# transceiver_2.net
KiCad netlist of a schematic drawn in EAGLE
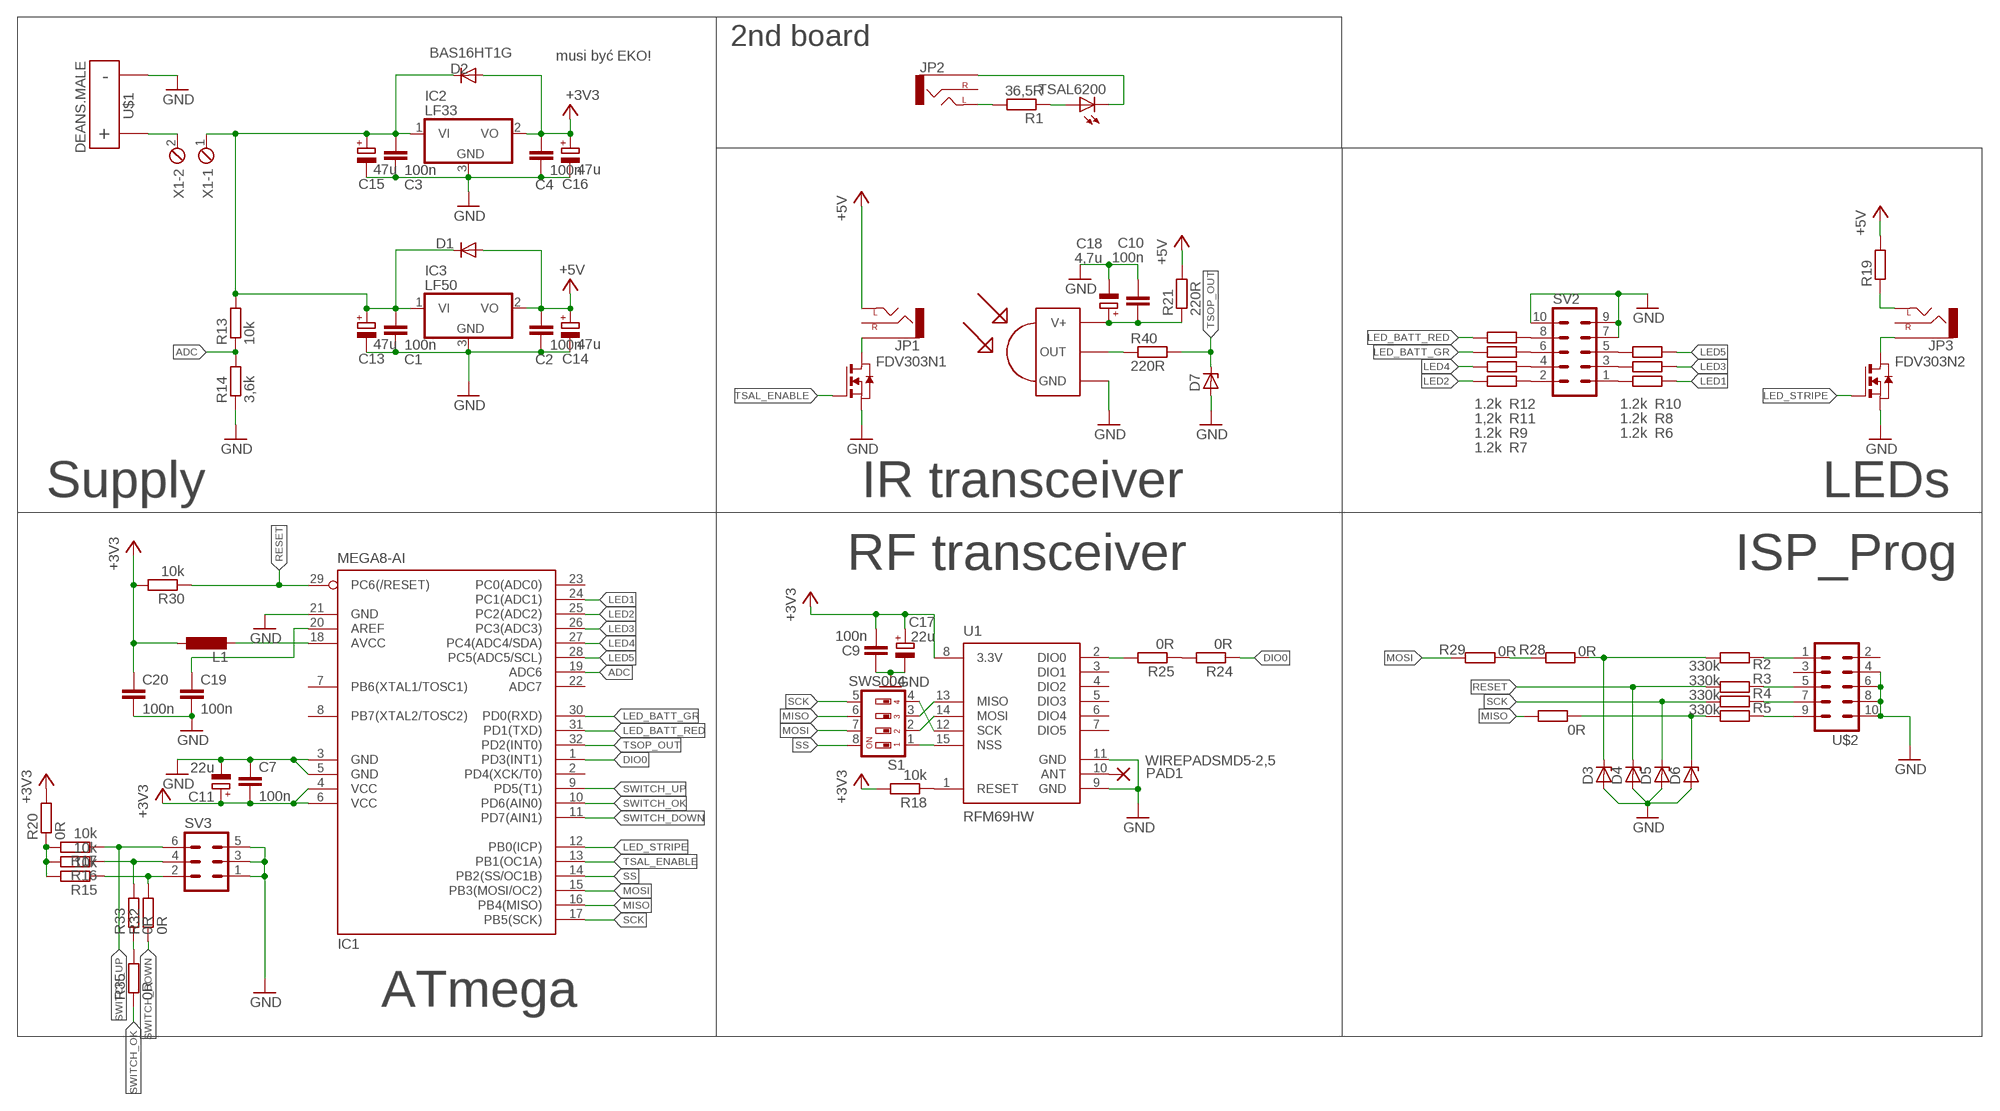
[diagram p0: schematic, sheet 1]

(export (version "E")
  (design (tool "Eeschema 10.0.6"))
  (components
    (comp (ref "C1")
      (value "100n")
      (footprint "eagle-import:C0805")
      (libsource (lib "eagle-import") (part "C-EUC0805"))
    )
    (comp (ref "C2")
      (value "100n")
      (footprint "eagle-import:C0805")
      (libsource (lib "eagle-import") (part "C-EUC0805"))
    )
    (comp (ref "C3")
      (value "100n")
      (footprint "eagle-import:C0805")
      (libsource (lib "eagle-import") (part "C-EUC0805"))
    )
    (comp (ref "C4")
      (value "100n")
      (footprint "eagle-import:C0805")
      (libsource (lib "eagle-import") (part "C-EUC0805"))
    )
    (comp (ref "C7")
      (value "100n")
      (footprint "eagle-import:C0805")
      (libsource (lib "eagle-import") (part "C-EUC0805"))
    )
    (comp (ref "C9")
      (value "100n")
      (footprint "eagle-import:C0805")
      (libsource (lib "eagle-import") (part "C-EUC0805"))
    )
    (comp (ref "C10")
      (value "100n")
      (footprint "eagle-import:C0805")
      (libsource (lib "eagle-import") (part "C-EUC0805"))
    )
    (comp (ref "C11")
      (value "22u")
      (footprint "eagle-import:E2,5-5")
      (libsource (lib "eagle-import") (part "CPOL-EUE2.5-5"))
    )
    (comp (ref "C13")
      (value "47u")
      (footprint "eagle-import:E2,5-5")
      (libsource (lib "eagle-import") (part "CPOL-EUE2.5-5"))
    )
    (comp (ref "C14")
      (value "47u")
      (footprint "eagle-import:E2,5-5")
      (libsource (lib "eagle-import") (part "CPOL-EUE2.5-5"))
    )
    (comp (ref "C15")
      (value "47u")
      (footprint "eagle-import:E2,5-5")
      (libsource (lib "eagle-import") (part "CPOL-EUE2.5-5"))
    )
    (comp (ref "C16")
      (value "47u")
      (footprint "eagle-import:E2,5-5")
      (libsource (lib "eagle-import") (part "CPOL-EUE2.5-5"))
    )
    (comp (ref "C17")
      (value "22u")
      (footprint "eagle-import:E2,5-5")
      (libsource (lib "eagle-import") (part "CPOL-EUE2.5-5"))
    )
    (comp (ref "C18")
      (value "4,7u")
      (footprint "eagle-import:E2,5-5")
      (libsource (lib "eagle-import") (part "CPOL-EUE2.5-5"))
    )
    (comp (ref "C19")
      (value "100n")
      (footprint "eagle-import:C0805")
      (libsource (lib "eagle-import") (part "C-EUC0805"))
    )
    (comp (ref "C20")
      (value "100n")
      (footprint "eagle-import:C0805")
      (libsource (lib "eagle-import") (part "C-EUC0805"))
    )
    (comp (ref "D1")
      (value "BAS16HT1G")
      (footprint "eagle-import:SOD-323")
      (libsource (lib "eagle-import") (part "DIODESOD"))
    )
    (comp (ref "D2")
      (value "BAS16HT1G")
      (footprint "eagle-import:SOD-323")
      (libsource (lib "eagle-import") (part "DIODESOD"))
    )
    (comp (ref "D3")
      (value "ZENER-DIODESOD80C")
      (footprint "eagle-import:SOD80C")
      (libsource (lib "eagle-import") (part "ZENER-DIODESOD80C"))
    )
    (comp (ref "D4")
      (value "ZENER-DIODESOD80C")
      (footprint "eagle-import:SOD80C")
      (libsource (lib "eagle-import") (part "ZENER-DIODESOD80C"))
    )
    (comp (ref "D5")
      (value "ZENER-DIODESOD80C")
      (footprint "eagle-import:SOD80C")
      (libsource (lib "eagle-import") (part "ZENER-DIODESOD80C"))
    )
    (comp (ref "D6")
      (value "ZENER-DIODESOD80C")
      (footprint "eagle-import:SOD80C")
      (libsource (lib "eagle-import") (part "ZENER-DIODESOD80C"))
    )
    (comp (ref "D7")
      (value "ZENER-DIODESOD80C")
      (footprint "eagle-import:SOD80C")
      (libsource (lib "eagle-import") (part "ZENER-DIODESOD80C"))
    )
    (comp (ref "FDV303N1")
      (value "NMOSSOT23")
      (footprint "eagle-import:SOT-23")
      (libsource (lib "eagle-import") (part "NMOSSOT23"))
    )
    (comp (ref "FDV303N2")
      (value "NMOSSOT23")
      (footprint "eagle-import:SOT-23")
      (libsource (lib "eagle-import") (part "NMOSSOT23"))
    )
    (comp (ref "IC1")
      (value "MEGA8-AI")
      (footprint "eagle-import:TQFP32-08")
      (fields (field (name "MPN") "ATMEGA8-16AU"))
      (libsource (lib "eagle-import") (part "MEGA8-AI"))
    )
    (comp (ref "IC2")
      (value "LF33")
      (footprint "eagle-import:TO252")
      (libsource (lib "eagle-import") (part "78DT05"))
    )
    (comp (ref "IC3")
      (value "LF50")
      (footprint "eagle-import:TO252")
      (libsource (lib "eagle-import") (part "78DT05"))
    )
    (comp (ref "JP1")
      (value "AUDIO-JACKPTH")
      (footprint "eagle-import:AUDIO-JACK")
      (libsource (lib "eagle-import") (part "AUDIO-JACKPTH"))
    )
    (comp (ref "JP2")
      (value "AUDIO-JACKPTH")
      (footprint "eagle-import:AUDIO-JACK")
      (libsource (lib "eagle-import") (part "AUDIO-JACKPTH"))
    )
    (comp (ref "JP3")
      (value "AUDIO-JACKPTH")
      (footprint "eagle-import:AUDIO-JACK")
      (libsource (lib "eagle-import") (part "AUDIO-JACKPTH"))
    )
    (comp (ref "L1")
      (value "L-EU0204V")
      (footprint "eagle-import:0204V")
      (libsource (lib "eagle-import") (part "L-EU0204V"))
    )
    (comp (ref "PAD1")
      (value "WIREPADSMD5-2,5")
      (footprint "eagle-import:5-2,5")
      (libsource (lib "eagle-import") (part "WIREPADSMD5-2,5"))
    )
    (comp (ref "R1")
      (value "36,5R")
      (footprint "eagle-import:R0805")
      (libsource (lib "eagle-import") (part "resistor_R-EU_R0805"))
    )
    (comp (ref "R2")
      (value "330k")
      (footprint "eagle-import:R0805")
      (libsource (lib "eagle-import") (part "resistor_R-EU_R0805"))
    )
    (comp (ref "R3")
      (value "330k")
      (footprint "eagle-import:R0805")
      (libsource (lib "eagle-import") (part "resistor_R-EU_R0805"))
    )
    (comp (ref "R4")
      (value "330k")
      (footprint "eagle-import:R0805")
      (libsource (lib "eagle-import") (part "resistor_R-EU_R0805"))
    )
    (comp (ref "R5")
      (value "330k")
      (footprint "eagle-import:R0805")
      (libsource (lib "eagle-import") (part "resistor_R-EU_R0805"))
    )
    (comp (ref "R6")
      (value "1.2k")
      (footprint "eagle-import:R0805")
      (libsource (lib "eagle-import") (part "resistor_R-EU_R0805"))
    )
    (comp (ref "R7")
      (value "1.2k")
      (footprint "eagle-import:R0805")
      (libsource (lib "eagle-import") (part "resistor_R-EU_R0805"))
    )
    (comp (ref "R8")
      (value "1.2k")
      (footprint "eagle-import:R0805")
      (libsource (lib "eagle-import") (part "resistor_R-EU_R0805"))
    )
    (comp (ref "R9")
      (value "1.2k")
      (footprint "eagle-import:R0805")
      (libsource (lib "eagle-import") (part "resistor_R-EU_R0805"))
    )
    (comp (ref "R10")
      (value "1.2k")
      (footprint "eagle-import:R0805")
      (libsource (lib "eagle-import") (part "resistor_R-EU_R0805"))
    )
    (comp (ref "R11")
      (value "1,2k")
      (footprint "eagle-import:R0805")
      (libsource (lib "eagle-import") (part "resistor_R-EU_R0805"))
    )
    (comp (ref "R12")
      (value "1.2k")
      (footprint "eagle-import:R0805")
      (libsource (lib "eagle-import") (part "resistor_R-EU_R0805"))
    )
    (comp (ref "R13")
      (value "10k")
      (footprint "eagle-import:R0805")
      (libsource (lib "eagle-import") (part "resistor_R-EU_R0805"))
    )
    (comp (ref "R14")
      (value "3,6k")
      (footprint "eagle-import:R0805")
      (libsource (lib "eagle-import") (part "resistor_R-EU_R0805"))
    )
    (comp (ref "R15")
      (value "10k")
      (footprint "eagle-import:R0805")
      (libsource (lib "eagle-import") (part "resistor_R-EU_R0805"))
    )
    (comp (ref "R16")
      (value "10k")
      (footprint "eagle-import:R0805")
      (libsource (lib "eagle-import") (part "resistor_R-EU_R0805"))
    )
    (comp (ref "R17")
      (value "10k")
      (footprint "eagle-import:R0805")
      (libsource (lib "eagle-import") (part "resistor_R-EU_R0805"))
    )
    (comp (ref "R18")
      (value "10k")
      (footprint "eagle-import:R0805")
      (libsource (lib "eagle-import") (part "resistor_R-EU_R0805"))
    )
    (comp (ref "R19")
      (value "R-EU_R0805")
      (footprint "eagle-import:R0805")
      (libsource (lib "eagle-import") (part "resistor_R-EU_R0805"))
    )
    (comp (ref "R20")
      (value "0R")
      (footprint "eagle-import:R1206")
      (libsource (lib "eagle-import") (part "R-EU_R1206"))
    )
    (comp (ref "R21")
      (value "220R")
      (footprint "eagle-import:R0805")
      (libsource (lib "eagle-import") (part "resistor_R-EU_R0805"))
    )
    (comp (ref "R24")
      (value "0R")
      (footprint "eagle-import:R1206")
      (libsource (lib "eagle-import") (part "R-EU_R1206"))
    )
    (comp (ref "R25")
      (value "0R")
      (footprint "eagle-import:R1206")
      (libsource (lib "eagle-import") (part "R-EU_R1206"))
    )
    (comp (ref "R28")
      (value "0R")
      (footprint "eagle-import:R1206")
      (libsource (lib "eagle-import") (part "R-EU_R1206"))
    )
    (comp (ref "R29")
      (value "0R")
      (footprint "eagle-import:R1206")
      (libsource (lib "eagle-import") (part "R-EU_R1206"))
    )
    (comp (ref "R30")
      (value "10k")
      (footprint "eagle-import:R0805")
      (libsource (lib "eagle-import") (part "resistor_R-EU_R0805"))
    )
    (comp (ref "R31")
      (value "0R")
      (footprint "eagle-import:R1206")
      (libsource (lib "eagle-import") (part "R-EU_R1206"))
    )
    (comp (ref "R32")
      (value "0R")
      (footprint "eagle-import:R1206")
      (libsource (lib "eagle-import") (part "R-EU_R1206"))
    )
    (comp (ref "R33")
      (value "0R")
      (footprint "eagle-import:R1206")
      (libsource (lib "eagle-import") (part "R-EU_R1206"))
    )
    (comp (ref "R35")
      (value "0R")
      (footprint "eagle-import:R1206")
      (libsource (lib "eagle-import") (part "R-EU_R1206"))
    )
    (comp (ref "R40")
      (value "220R")
      (footprint "eagle-import:R0805")
      (libsource (lib "eagle-import") (part "resistor_R-EU_R0805"))
    )
    (comp (ref "S1")
      (value "SWS004")
      (footprint "eagle-import:SMS-004")
      (libsource (lib "eagle-import") (part "SWS004"))
    )
    (comp (ref "SV2")
      (value "ML10")
      (footprint "eagle-import:ML10")
      (libsource (lib "eagle-import") (part "ML10"))
    )
    (comp (ref "SV3")
      (value "ML6")
      (footprint "eagle-import:ML6")
      (libsource (lib "eagle-import") (part "ML6"))
    )
    (comp (ref "TSAL6200")
      (value "LED5MM")
      (footprint "eagle-import:LED5MM")
      (libsource (lib "eagle-import") (part "LED5MM"))
    )
    (comp (ref "TSOP")
      (value "TSOP1736")
      (footprint "eagle-import:TSOP17XX")
      (libsource (lib "eagle-import") (part "TSOP1736"))
    )
    (comp (ref "U$1")
      (value "DEANS.MALE")
      (footprint "eagle-import:DEANSM")
      (libsource (lib "eagle-import") (part "DEANS.MALE"))
    )
    (comp (ref "U$2")
      (value "ML10")
      (footprint "eagle-import:ML10")
      (libsource (lib "eagle-import") (part "ML10"))
    )
    (comp (ref "U1")
      (value "RFM69HW")
      (footprint "eagle-import:RFM69W-XXXS2")
      (libsource (lib "eagle-import") (part "RFM69HW"))
    )
    (comp (ref "X1")
      (value "MPT2")
      (footprint "eagle-import:2POL254")
      (libsource (lib "eagle-import") (part "MPT2"))
    )
  )
  (nets
    (net (code "1") (name "+3V3") (class "Default")
      (node (ref "C11") (pin "+") (pinfunction "+_+") (pintype "passive"))
      (node (ref "C16") (pin "+") (pinfunction "+_+") (pintype "passive"))
      (node (ref "C17") (pin "+") (pinfunction "+_+") (pintype "passive"))
      (node (ref "C20") (pin "1") (pinfunction "1_1") (pintype "passive"))
      (node (ref "C4") (pin "1") (pinfunction "1_1") (pintype "passive"))
      (node (ref "C7") (pin "2") (pinfunction "2_2") (pintype "passive"))
      (node (ref "C9") (pin "2") (pinfunction "2_2") (pintype "passive"))
      (node (ref "D2") (pin "2") (pinfunction "A_2") (pintype "passive"))
      (node (ref "IC1") (pin "4") (pinfunction "VCC_4") (pintype "power_in"))
      (node (ref "IC1") (pin "6") (pinfunction "VCC_6") (pintype "power_in"))
      (node (ref "IC2") (pin "2") (pinfunction "VO_2") (pintype "passive"))
      (node (ref "L1") (pin "1") (pinfunction "1_1") (pintype "passive"))
      (node (ref "R18") (pin "2") (pinfunction "2_2") (pintype "passive"))
      (node (ref "R20") (pin "2") (pinfunction "2_2") (pintype "passive"))
      (node (ref "R30") (pin "2") (pinfunction "2_2") (pintype "passive"))
      (node (ref "U1") (pin "8") (pinfunction "3.3V_8") (pintype "power_in"))
    )
    (net (code "2") (name "+5V") (class "Default")
      (node (ref "C14") (pin "+") (pinfunction "+_+") (pintype "passive"))
      (node (ref "C2") (pin "1") (pinfunction "1_1") (pintype "passive"))
      (node (ref "D1") (pin "2") (pinfunction "A_2") (pintype "passive"))
      (node (ref "IC3") (pin "2") (pinfunction "VO_2") (pintype "passive"))
      (node (ref "JP1") (pin "TIP") (pinfunction "LEFT_TIP") (pintype "bidirectional"))
      (node (ref "R19") (pin "2") (pinfunction "2_2") (pintype "passive"))
      (node (ref "R21") (pin "2") (pinfunction "2_2") (pintype "passive"))
    )
    (net (code "3") (name "ADC") (class "Default")
      (node (ref "IC1") (pin "19") (pinfunction "ADC6_19") (pintype "bidirectional"))
      (node (ref "R13") (pin "1") (pinfunction "1_1") (pintype "passive"))
      (node (ref "R14") (pin "2") (pinfunction "2_2") (pintype "passive"))
    )
    (net (code "4") (name "DIO0") (class "Default")
      (node (ref "IC1") (pin "1") (pinfunction "PD3(INT1)_1") (pintype "bidirectional"))
      (node (ref "R24") (pin "1") (pinfunction "1_1") (pintype "passive"))
    )
    (net (code "5") (name "GND") (class "Default")
      (node (ref "C1") (pin "2") (pinfunction "2_2") (pintype "passive"))
      (node (ref "C10") (pin "2") (pinfunction "2_2") (pintype "passive"))
      (node (ref "C11") (pin "-") (pinfunction "-_-") (pintype "passive"))
      (node (ref "C13") (pin "-") (pinfunction "-_-") (pintype "passive"))
      (node (ref "C14") (pin "-") (pinfunction "-_-") (pintype "passive"))
      (node (ref "C15") (pin "-") (pinfunction "-_-") (pintype "passive"))
      (node (ref "C16") (pin "-") (pinfunction "-_-") (pintype "passive"))
      (node (ref "C17") (pin "-") (pinfunction "-_-") (pintype "passive"))
      (node (ref "C18") (pin "-") (pinfunction "-_-") (pintype "passive"))
      (node (ref "C19") (pin "2") (pinfunction "2_2") (pintype "passive"))
      (node (ref "C2") (pin "2") (pinfunction "2_2") (pintype "passive"))
      (node (ref "C20") (pin "2") (pinfunction "2_2") (pintype "passive"))
      (node (ref "C3") (pin "2") (pinfunction "2_2") (pintype "passive"))
      (node (ref "C4") (pin "2") (pinfunction "2_2") (pintype "passive"))
      (node (ref "C7") (pin "1") (pinfunction "1_1") (pintype "passive"))
      (node (ref "C9") (pin "1") (pinfunction "1_1") (pintype "passive"))
      (node (ref "D3") (pin "A") (pinfunction "A_A") (pintype "passive"))
      (node (ref "D4") (pin "A") (pinfunction "A_A") (pintype "passive"))
      (node (ref "D5") (pin "A") (pinfunction "A_A") (pintype "passive"))
      (node (ref "D6") (pin "A") (pinfunction "A_A") (pintype "passive"))
      (node (ref "D7") (pin "A") (pinfunction "A_A") (pintype "passive"))
      (node (ref "FDV303N1") (pin "2") (pinfunction "S_2") (pintype "passive"))
      (node (ref "FDV303N2") (pin "2") (pinfunction "S_2") (pintype "passive"))
      (node (ref "IC1") (pin "21") (pinfunction "GND_21") (pintype "power_in"))
      (node (ref "IC1") (pin "3") (pinfunction "GND_3") (pintype "power_in"))
      (node (ref "IC1") (pin "5") (pinfunction "GND_5") (pintype "power_in"))
      (node (ref "IC2") (pin "3") (pinfunction "GND_3") (pintype "passive"))
      (node (ref "IC3") (pin "3") (pinfunction "GND_3") (pintype "passive"))
      (node (ref "R14") (pin "1") (pinfunction "1_1") (pintype "passive"))
      (node (ref "SV2") (pin "10") (pinfunction "10_10") (pintype "passive"))
      (node (ref "SV2") (pin "7") (pinfunction "7_7") (pintype "passive"))
      (node (ref "SV2") (pin "9") (pinfunction "9_9") (pintype "passive"))
      (node (ref "SV3") (pin "1") (pinfunction "1_1") (pintype "passive"))
      (node (ref "SV3") (pin "3") (pinfunction "3_3") (pintype "passive"))
      (node (ref "SV3") (pin "5") (pinfunction "5_5") (pintype "passive"))
      (node (ref "TSOP") (pin "GND") (pinfunction "GND_GND") (pintype "bidirectional"))
      (node (ref "U$1") (pin "P$NEG") (pinfunction "P$NEG_P$NEG") (pintype "bidirectional"))
      (node (ref "U$2") (pin "10") (pinfunction "10_10") (pintype "passive"))
      (node (ref "U$2") (pin "4") (pinfunction "4_4") (pintype "passive"))
      (node (ref "U$2") (pin "6") (pinfunction "6_6") (pintype "passive"))
      (node (ref "U$2") (pin "8") (pinfunction "8_8") (pintype "passive"))
      (node (ref "U1") (pin "11") (pinfunction "GND_11") (pintype "power_in"))
      (node (ref "U1") (pin "9") (pinfunction "GND_9") (pintype "power_in"))
    )
    (net (code "6") (name "LED1") (class "Default")
      (node (ref "IC1") (pin "24") (pinfunction "PC1(ADC1)_24") (pintype "bidirectional"))
      (node (ref "R6") (pin "1") (pinfunction "1_1") (pintype "passive"))
    )
    (net (code "7") (name "LED2") (class "Default")
      (node (ref "IC1") (pin "25") (pinfunction "PC2(ADC2)_25") (pintype "bidirectional"))
      (node (ref "R7") (pin "1") (pinfunction "1_1") (pintype "passive"))
    )
    (net (code "8") (name "LED3") (class "Default")
      (node (ref "IC1") (pin "26") (pinfunction "PC3(ADC3)_26") (pintype "bidirectional"))
      (node (ref "R8") (pin "1") (pinfunction "1_1") (pintype "passive"))
    )
    (net (code "9") (name "LED4") (class "Default")
      (node (ref "IC1") (pin "27") (pinfunction "PC4(ADC4/SDA)_27") (pintype "bidirectional"))
      (node (ref "R9") (pin "1") (pinfunction "1_1") (pintype "passive"))
    )
    (net (code "10") (name "LED5") (class "Default")
      (node (ref "IC1") (pin "28") (pinfunction "PC5(ADC5/SCL)_28") (pintype "bidirectional"))
      (node (ref "R10") (pin "1") (pinfunction "1_1") (pintype "passive"))
    )
    (net (code "11") (name "LED_BATT_GR") (class "Default")
      (node (ref "IC1") (pin "30") (pinfunction "PD0(RXD)_30") (pintype "bidirectional"))
      (node (ref "R11") (pin "1") (pinfunction "1_1") (pintype "passive"))
    )
    (net (code "12") (name "LED_BATT_RED") (class "Default")
      (node (ref "IC1") (pin "31") (pinfunction "PD1(TXD)_31") (pintype "bidirectional"))
      (node (ref "R12") (pin "1") (pinfunction "1_1") (pintype "passive"))
    )
    (net (code "13") (name "LED_STRIPE") (class "Default")
      (node (ref "FDV303N2") (pin "3") (pinfunction "G_3") (pintype "passive"))
      (node (ref "IC1") (pin "12") (pinfunction "PB0(ICP)_12") (pintype "bidirectional"))
    )
    (net (code "14") (name "MISO") (class "Default")
      (node (ref "IC1") (pin "16") (pinfunction "PB4(MISO)_16") (pintype "bidirectional"))
      (node (ref "R31") (pin "2") (pinfunction "2_2") (pintype "passive"))
      (node (ref "S1") (pin "6") (pinfunction "6_6") (pintype "passive"))
    )
    (net (code "15") (name "MOSI") (class "Default")
      (node (ref "IC1") (pin "15") (pinfunction "PB3(MOSI/OC2)_15") (pintype "bidirectional"))
      (node (ref "R29") (pin "2") (pinfunction "2_2") (pintype "passive"))
      (node (ref "S1") (pin "7") (pinfunction "7_7") (pintype "passive"))
    )
    (net (code "16") (name "Net-(C10-Pad1)") (class "Default")
      (node (ref "C10") (pin "1") (pinfunction "1_1") (pintype "passive"))
      (node (ref "C18") (pin "+") (pinfunction "+_+") (pintype "passive"))
      (node (ref "R21") (pin "1") (pinfunction "1_1") (pintype "passive"))
      (node (ref "TSOP") (pin "V+") (pinfunction "V+_V+") (pintype "bidirectional"))
    )
    (net (code "17") (name "Net-(D1-C)") (class "Default")
      (node (ref "C1") (pin "1") (pinfunction "1_1") (pintype "passive"))
      (node (ref "C13") (pin "+") (pinfunction "+_+") (pintype "passive"))
      (node (ref "C15") (pin "+") (pinfunction "+_+") (pintype "passive"))
      (node (ref "C3") (pin "1") (pinfunction "1_1") (pintype "passive"))
      (node (ref "D1") (pin "1") (pinfunction "C_1") (pintype "passive"))
      (node (ref "D2") (pin "1") (pinfunction "C_1") (pintype "passive"))
      (node (ref "IC2") (pin "1") (pinfunction "VI_1") (pintype "input"))
      (node (ref "IC3") (pin "1") (pinfunction "VI_1") (pintype "input"))
      (node (ref "R13") (pin "2") (pinfunction "2_2") (pintype "passive"))
      (node (ref "X1") (pin "1") (pinfunction "1_1") (pintype "passive"))
    )
    (net (code "18") (name "Net-(D3-PadC)") (class "Default")
      (node (ref "D3") (pin "C") (pinfunction "C_C") (pintype "passive"))
      (node (ref "R2") (pin "2") (pinfunction "2_2") (pintype "passive"))
      (node (ref "R28") (pin "1") (pinfunction "1_1") (pintype "passive"))
    )
    (net (code "19") (name "Net-(D6-PadC)") (class "Default")
      (node (ref "D6") (pin "C") (pinfunction "C_C") (pintype "passive"))
      (node (ref "R31") (pin "1") (pinfunction "1_1") (pintype "passive"))
      (node (ref "R5") (pin "2") (pinfunction "2_2") (pintype "passive"))
    )
    (net (code "20") (name "Net-(FDV303N1-D)") (class "Default")
      (node (ref "FDV303N1") (pin "1") (pinfunction "D_1") (pintype "passive"))
      (node (ref "JP1") (pin "SLEEVE") (pinfunction "SLEEVE_SLEEVE") (pintype "bidirectional"))
    )
    (net (code "21") (name "Net-(FDV303N2-D)") (class "Default")
      (node (ref "FDV303N2") (pin "1") (pinfunction "D_1") (pintype "passive"))
      (node (ref "JP3") (pin "SLEEVE") (pinfunction "SLEEVE_SLEEVE") (pintype "bidirectional"))
    )
    (net (code "22") (name "Net-(IC1-AREF)") (class "Default")
      (node (ref "C19") (pin "1") (pinfunction "1_1") (pintype "passive"))
      (node (ref "IC1") (pin "20") (pinfunction "AREF_20") (pintype "passive"))
    )
    (net (code "23") (name "Net-(IC1-AVCC)") (class "Default")
      (node (ref "IC1") (pin "18") (pinfunction "AVCC_18") (pintype "power_in"))
      (node (ref "L1") (pin "2") (pinfunction "2_2") (pintype "passive"))
    )
    (net (code "24") (name "Net-(JP2-LEFT)") (class "Default")
      (node (ref "JP2") (pin "TIP") (pinfunction "LEFT_TIP") (pintype "bidirectional"))
      (node (ref "R1") (pin "2") (pinfunction "2_2") (pintype "passive"))
    )
    (net (code "25") (name "Net-(JP3-LEFT)") (class "Default")
      (node (ref "JP3") (pin "TIP") (pinfunction "LEFT_TIP") (pintype "bidirectional"))
      (node (ref "R19") (pin "1") (pinfunction "1_1") (pintype "passive"))
    )
    (net (code "26") (name "Net-(PAD1-P)") (class "Default")
      (node (ref "PAD1") (pin "1") (pinfunction "P_1") (pintype "passive"))
      (node (ref "U1") (pin "10") (pinfunction "ANT_10") (pintype "passive"))
    )
    (net (code "27") (name "Net-(R1-Pad1)") (class "Default")
      (node (ref "R1") (pin "1") (pinfunction "1_1") (pintype "passive"))
      (node (ref "TSAL6200") (pin "A") (pinfunction "A_A") (pintype "passive"))
    )
    (net (code "28") (name "Net-(R2-Pad1)") (class "Default")
      (node (ref "R2") (pin "1") (pinfunction "1_1") (pintype "passive"))
      (node (ref "U$2") (pin "1") (pinfunction "1_1") (pintype "passive"))
    )
    (net (code "29") (name "Net-(R3-Pad1)") (class "Default")
      (node (ref "R3") (pin "1") (pinfunction "1_1") (pintype "passive"))
      (node (ref "U$2") (pin "5") (pinfunction "5_5") (pintype "passive"))
    )
    (net (code "30") (name "Net-(R4-Pad1)") (class "Default")
      (node (ref "R4") (pin "1") (pinfunction "1_1") (pintype "passive"))
      (node (ref "U$2") (pin "7") (pinfunction "7_7") (pintype "passive"))
    )
    (net (code "31") (name "Net-(R5-Pad1)") (class "Default")
      (node (ref "R5") (pin "1") (pinfunction "1_1") (pintype "passive"))
      (node (ref "U$2") (pin "9") (pinfunction "9_9") (pintype "passive"))
    )
    (net (code "32") (name "Net-(R6-Pad2)") (class "Default")
      (node (ref "R6") (pin "2") (pinfunction "2_2") (pintype "passive"))
      (node (ref "SV2") (pin "1") (pinfunction "1_1") (pintype "passive"))
    )
    (net (code "33") (name "Net-(R7-Pad2)") (class "Default")
      (node (ref "R7") (pin "2") (pinfunction "2_2") (pintype "passive"))
      (node (ref "SV2") (pin "2") (pinfunction "2_2") (pintype "passive"))
    )
    (net (code "34") (name "Net-(R8-Pad2)") (class "Default")
      (node (ref "R8") (pin "2") (pinfunction "2_2") (pintype "passive"))
      (node (ref "SV2") (pin "3") (pinfunction "3_3") (pintype "passive"))
    )
    (net (code "35") (name "Net-(R9-Pad2)") (class "Default")
      (node (ref "R9") (pin "2") (pinfunction "2_2") (pintype "passive"))
      (node (ref "SV2") (pin "4") (pinfunction "4_4") (pintype "passive"))
    )
    (net (code "36") (name "Net-(R10-Pad2)") (class "Default")
      (node (ref "R10") (pin "2") (pinfunction "2_2") (pintype "passive"))
      (node (ref "SV2") (pin "5") (pinfunction "5_5") (pintype "passive"))
    )
    (net (code "37") (name "Net-(R11-Pad2)") (class "Default")
      (node (ref "R11") (pin "2") (pinfunction "2_2") (pintype "passive"))
      (node (ref "SV2") (pin "6") (pinfunction "6_6") (pintype "passive"))
    )
    (net (code "38") (name "Net-(R12-Pad2)") (class "Default")
      (node (ref "R12") (pin "2") (pinfunction "2_2") (pintype "passive"))
      (node (ref "SV2") (pin "8") (pinfunction "8_8") (pintype "passive"))
    )
    (net (code "39") (name "Net-(R15-Pad1)") (class "Default")
      (node (ref "R15") (pin "1") (pinfunction "1_1") (pintype "passive"))
      (node (ref "R32") (pin "2") (pinfunction "2_2") (pintype "passive"))
      (node (ref "SV3") (pin "2") (pinfunction "2_2") (pintype "passive"))
    )
    (net (code "40") (name "Net-(R15-Pad2)") (class "Default")
      (node (ref "R15") (pin "2") (pinfunction "2_2") (pintype "passive"))
      (node (ref "R16") (pin "2") (pinfunction "2_2") (pintype "passive"))
      (node (ref "R17") (pin "2") (pinfunction "2_2") (pintype "passive"))
      (node (ref "R20") (pin "1") (pinfunction "1_1") (pintype "passive"))
    )
    (net (code "41") (name "Net-(R16-Pad1)") (class "Default")
      (node (ref "R16") (pin "1") (pinfunction "1_1") (pintype "passive"))
      (node (ref "R33") (pin "2") (pinfunction "2_2") (pintype "passive"))
      (node (ref "SV3") (pin "4") (pinfunction "4_4") (pintype "passive"))
    )
    (net (code "42") (name "Net-(R24-Pad2)") (class "Default")
      (node (ref "R24") (pin "2") (pinfunction "2_2") (pintype "passive"))
      (node (ref "R25") (pin "1") (pinfunction "1_1") (pintype "passive"))
    )
    (net (code "43") (name "Net-(R28-Pad2)") (class "Default")
      (node (ref "R28") (pin "2") (pinfunction "2_2") (pintype "passive"))
      (node (ref "R29") (pin "1") (pinfunction "1_1") (pintype "passive"))
    )
    (net (code "44") (name "Net-(R33-Pad1)") (class "Default")
      (node (ref "R33") (pin "1") (pinfunction "1_1") (pintype "passive"))
      (node (ref "R35") (pin "2") (pinfunction "2_2") (pintype "passive"))
    )
    (net (code "45") (name "Net-(R40-Pad1)") (class "Default")
      (node (ref "R40") (pin "1") (pinfunction "1_1") (pintype "passive"))
      (node (ref "TSOP") (pin "OUT") (pinfunction "OUT_OUT") (pintype "bidirectional"))
    )
    (net (code "46") (name "Net-(TSAL6200-C)") (class "Default")
      (node (ref "JP2") (pin "SLEEVE") (pinfunction "SLEEVE_SLEEVE") (pintype "bidirectional"))
      (node (ref "TSAL6200") (pin "K") (pinfunction "C_K") (pintype "passive"))
    )
    (net (code "47") (name "Net-(U1-DIO0)") (class "Default")
      (node (ref "R25") (pin "2") (pinfunction "2_2") (pintype "passive"))
      (node (ref "U1") (pin "2") (pinfunction "DIO0_2") (pintype "bidirectional"))
    )
    (net (code "48") (name "Net-(U1-MISO)") (class "Default")
      (node (ref "S1") (pin "3") (pinfunction "3_3") (pintype "passive"))
      (node (ref "U1") (pin "13") (pinfunction "MISO_13") (pintype "bidirectional"))
    )
    (net (code "49") (name "Net-(U1-MOSI)") (class "Default")
      (node (ref "S1") (pin "2") (pinfunction "2_2") (pintype "passive"))
      (node (ref "U1") (pin "14") (pinfunction "MOSI_14") (pintype "input"))
    )
    (net (code "50") (name "Net-(U1-NSS)") (class "Default")
      (node (ref "S1") (pin "1") (pinfunction "1_1") (pintype "passive"))
      (node (ref "U1") (pin "15") (pinfunction "NSS_15") (pintype "input"))
    )
    (net (code "51") (name "Net-(U1-RESET)") (class "Default")
      (node (ref "R18") (pin "1") (pinfunction "1_1") (pintype "passive"))
      (node (ref "U1") (pin "1") (pinfunction "RESET_1") (pintype "input"))
    )
    (net (code "52") (name "Net-(U1-SCK)") (class "Default")
      (node (ref "S1") (pin "4") (pinfunction "4_4") (pintype "passive"))
      (node (ref "U1") (pin "12") (pinfunction "SCK_12") (pintype "input"))
    )
    (net (code "53") (name "Net-(X1B-1)") (class "Default")
      (node (ref "U$1") (pin "P$POS") (pinfunction "P$POS_P$POS") (pintype "bidirectional"))
      (node (ref "X1") (pin "2") (pinfunction "1_2") (pintype "passive"))
    )
    (net (code "54") (name "RESET") (class "Default")
      (node (ref "D4") (pin "C") (pinfunction "C_C") (pintype "passive"))
      (node (ref "IC1") (pin "29") (pinfunction "PC6(/RESET)_29") (pintype "bidirectional"))
      (node (ref "R3") (pin "2") (pinfunction "2_2") (pintype "passive"))
      (node (ref "R30") (pin "1") (pinfunction "1_1") (pintype "passive"))
    )
    (net (code "55") (name "SCK") (class "Default")
      (node (ref "D5") (pin "C") (pinfunction "C_C") (pintype "passive"))
      (node (ref "IC1") (pin "17") (pinfunction "PB5(SCK)_17") (pintype "bidirectional"))
      (node (ref "R4") (pin "2") (pinfunction "2_2") (pintype "passive"))
      (node (ref "S1") (pin "5") (pinfunction "5_5") (pintype "passive"))
    )
    (net (code "56") (name "SS") (class "Default")
      (node (ref "IC1") (pin "14") (pinfunction "PB2(SS/OC1B)_14") (pintype "bidirectional"))
      (node (ref "S1") (pin "8") (pinfunction "8_8") (pintype "passive"))
    )
    (net (code "57") (name "SWITCH_DOWN") (class "Default")
      (node (ref "IC1") (pin "11") (pinfunction "PD7(AIN1)_11") (pintype "bidirectional"))
      (node (ref "R32") (pin "1") (pinfunction "1_1") (pintype "passive"))
    )
    (net (code "58") (name "SWITCH_OK") (class "Default")
      (node (ref "IC1") (pin "10") (pinfunction "PD6(AIN0)_10") (pintype "bidirectional"))
      (node (ref "R35") (pin "1") (pinfunction "1_1") (pintype "passive"))
    )
    (net (code "59") (name "SWITCH_UP") (class "Default")
      (node (ref "IC1") (pin "9") (pinfunction "PD5(T1)_9") (pintype "bidirectional"))
      (node (ref "R17") (pin "1") (pinfunction "1_1") (pintype "passive"))
      (node (ref "SV3") (pin "6") (pinfunction "6_6") (pintype "passive"))
    )
    (net (code "60") (name "TSAL_ENABLE") (class "Default")
      (node (ref "FDV303N1") (pin "3") (pinfunction "G_3") (pintype "passive"))
      (node (ref "IC1") (pin "13") (pinfunction "PB1(OC1A)_13") (pintype "bidirectional"))
    )
    (net (code "61") (name "TSOP_OUT") (class "Default")
      (node (ref "D7") (pin "C") (pinfunction "C_C") (pintype "passive"))
      (node (ref "IC1") (pin "32") (pinfunction "PD2(INT0)_32") (pintype "bidirectional"))
      (node (ref "R40") (pin "2") (pinfunction "2_2") (pintype "passive"))
    )
    (net (code "62") (name "unconnected-(IC1-ADC7-Pad22)") (class "Default")
      (node (ref "IC1") (pin "22") (pinfunction "ADC7_22") (pintype "bidirectional"))
    )
    (net (code "63") (name "unconnected-(IC1-PB6(XTAL1{slash}TOSC1)-Pad7)") (class "Default")
      (node (ref "IC1") (pin "7") (pinfunction "PB6(XTAL1/TOSC1)_7") (pintype "bidirectional"))
    )
    (net (code "64") (name "unconnected-(IC1-PB7(XTAL2{slash}TOSC2)-Pad8)") (class "Default")
      (node (ref "IC1") (pin "8") (pinfunction "PB7(XTAL2/TOSC2)_8") (pintype "bidirectional"))
    )
    (net (code "65") (name "unconnected-(IC1-PC0(ADC0)-Pad23)") (class "Default")
      (node (ref "IC1") (pin "23") (pinfunction "PC0(ADC0)_23") (pintype "bidirectional"))
    )
    (net (code "66") (name "unconnected-(IC1-PD4(XCK{slash}T0)-Pad2)") (class "Default")
      (node (ref "IC1") (pin "2") (pinfunction "PD4(XCK/T0)_2") (pintype "bidirectional"))
    )
    (net (code "67") (name "unconnected-(JP1-RIGHT-PadRING)") (class "Default")
      (node (ref "JP1") (pin "RING") (pinfunction "RIGHT_RING") (pintype "bidirectional"))
    )
    (net (code "68") (name "unconnected-(JP2-RIGHT-PadRING)") (class "Default")
      (node (ref "JP2") (pin "RING") (pinfunction "RIGHT_RING") (pintype "bidirectional"))
    )
    (net (code "69") (name "unconnected-(JP3-RIGHT-PadRING)") (class "Default")
      (node (ref "JP3") (pin "RING") (pinfunction "RIGHT_RING") (pintype "bidirectional"))
    )
    (net (code "70") (name "unconnected-(U$2-Pad2)") (class "Default")
      (node (ref "U$2") (pin "2") (pinfunction "2_2") (pintype "passive"))
    )
    (net (code "71") (name "unconnected-(U$2-Pad3)") (class "Default")
      (node (ref "U$2") (pin "3") (pinfunction "3_3") (pintype "passive"))
    )
    (net (code "72") (name "unconnected-(U1-DIO1-Pad3)") (class "Default")
      (node (ref "U1") (pin "3") (pinfunction "DIO1_3") (pintype "bidirectional"))
    )
    (net (code "73") (name "unconnected-(U1-DIO2-Pad4)") (class "Default")
      (node (ref "U1") (pin "4") (pinfunction "DIO2_4") (pintype "bidirectional"))
    )
    (net (code "74") (name "unconnected-(U1-DIO3-Pad5)") (class "Default")
      (node (ref "U1") (pin "5") (pinfunction "DIO3_5") (pintype "bidirectional"))
    )
    (net (code "75") (name "unconnected-(U1-DIO4-Pad6)") (class "Default")
      (node (ref "U1") (pin "6") (pinfunction "DIO4_6") (pintype "bidirectional"))
    )
    (net (code "76") (name "unconnected-(U1-DIO5-Pad7)") (class "Default")
      (node (ref "U1") (pin "7") (pinfunction "DIO5_7") (pintype "bidirectional"))
    )
  )
)
